# rf_lpf_60_40.net
KiCad netlist of a schematic drawn in Altium Designer
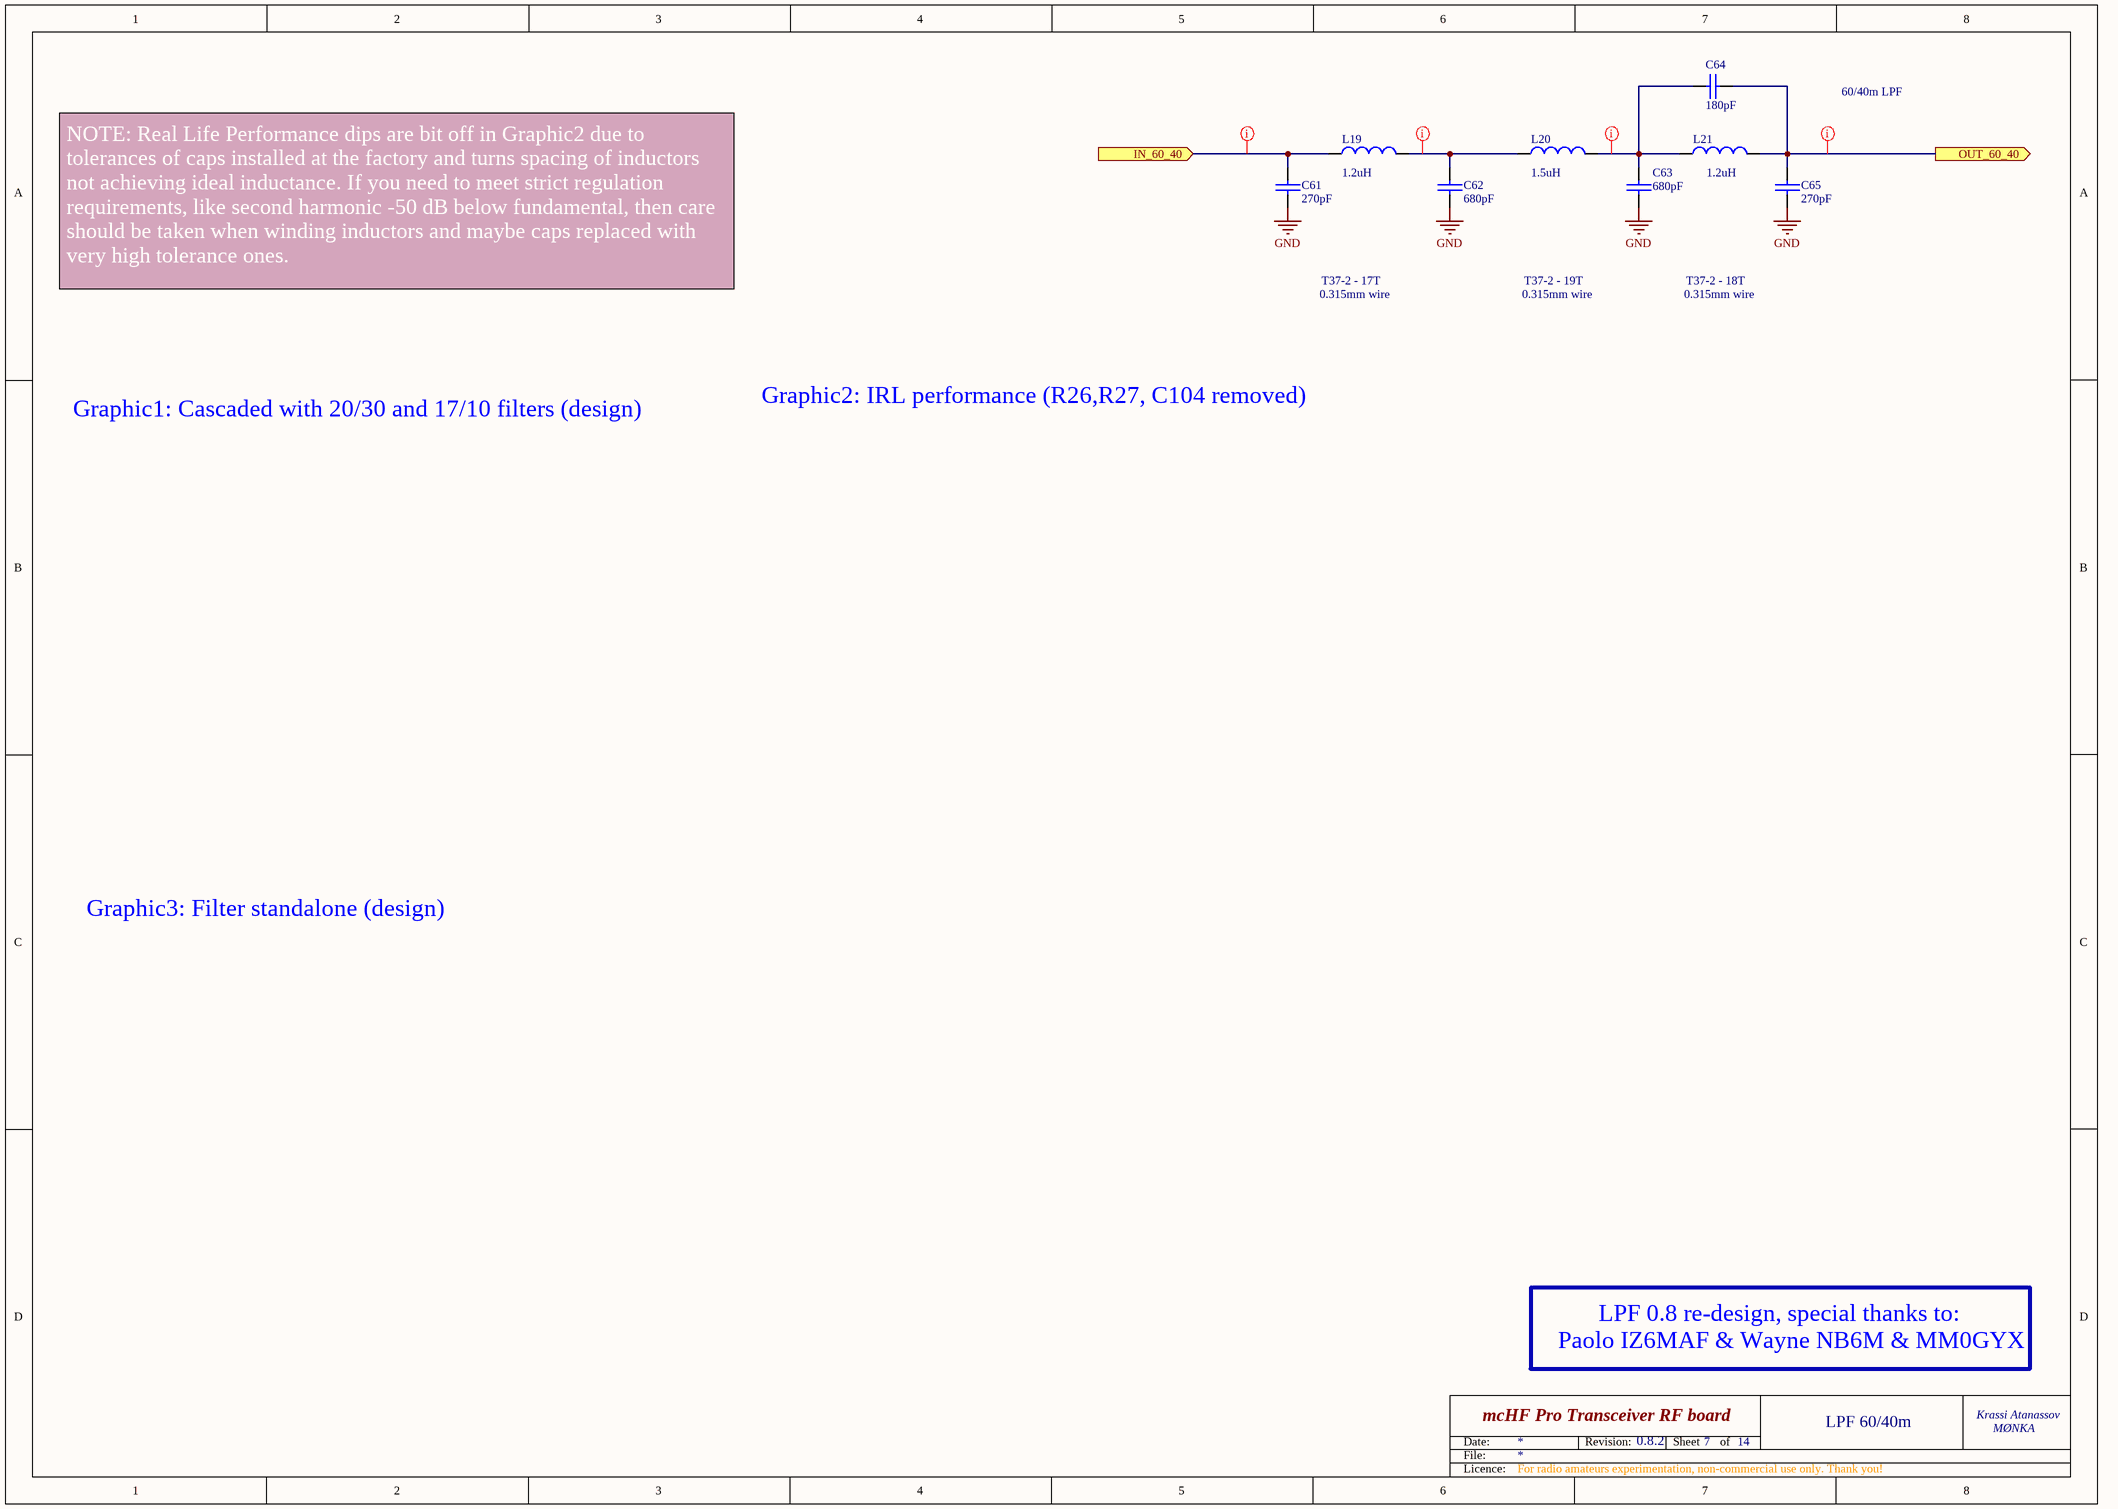
[diagram p0: rf_lpf_60_40.SchDoc]

(export (version "E")
  (design (tool "Eeschema 10.0.6"))
  (components
    (comp (ref "C61")
      (value "270pF")
      (footprint "0805")
      (description "Capacitor")
      (fields (field (name "VOLTAGE") "100V"))
      (libsource (lib "mcHF_rf") (part "CAP"))
    )
    (comp (ref "C62")
      (value "680pF")
      (footprint "0805")
      (description "Capacitor")
      (fields (field (name "VOLTAGE") "100V"))
      (libsource (lib "mcHF_rf") (part "CAP"))
    )
    (comp (ref "C63")
      (value "680pF")
      (footprint "0805")
      (description "Capacitor")
      (fields (field (name "VOLTAGE") "100V"))
      (libsource (lib "mcHF_rf") (part "CAP"))
    )
    (comp (ref "C64")
      (value "180pF")
      (footprint "0805")
      (description "Capacitor")
      (fields (field (name "VOLTAGE") "100V"))
      (libsource (lib "mcHF_rf") (part "CAP"))
    )
    (comp (ref "C65")
      (value "270pF")
      (footprint "0805")
      (description "Capacitor")
      (fields (field (name "VOLTAGE") "100V"))
      (libsource (lib "mcHF_rf") (part "CAP"))
    )
    (comp (ref "L19")
      (value "T37-2")
      (footprint "LPF_IND")
      (description "T37-2 handwound inductor")
      (fields (field (name "INDUCTANCE") "1.2uH"))
      (libsource (lib "mcHF_rf") (part "LPF_IND"))
    )
    (comp (ref "L20")
      (value "T37-2")
      (footprint "LPF_IND")
      (description "T37-2 handwound inductor")
      (fields (field (name "INDUCTANCE") "1.5uH"))
      (libsource (lib "mcHF_rf") (part "LPF_IND"))
    )
    (comp (ref "L21")
      (value "T37-2")
      (footprint "LPF_IND")
      (description "T37-2 handwound inductor")
      (fields (field (name "INDUCTANCE") "1.2uH"))
      (libsource (lib "mcHF_rf") (part "LPF_IND"))
    )
  )
  (nets
    (net (code "1") (name "/IN_60_40") (class "Default")
      (node (ref "C61") (pin "2") (pinfunction "2_2") (pintype "passive"))
      (node (ref "L19") (pin "1") (pinfunction "1_1") (pintype "passive"))
    )
    (net (code "2") (name "/OUT_60_40") (class "Default")
      (node (ref "C64") (pin "1") (pinfunction "1_1") (pintype "passive"))
      (node (ref "C65") (pin "2") (pinfunction "2_2") (pintype "passive"))
      (node (ref "L21") (pin "2") (pinfunction "2_2") (pintype "passive"))
    )
    (net (code "3") (name "GND") (class "Default")
      (node (ref "C61") (pin "1") (pinfunction "1_1") (pintype "passive"))
      (node (ref "C62") (pin "1") (pinfunction "1_1") (pintype "passive"))
      (node (ref "C63") (pin "1") (pinfunction "1_1") (pintype "passive"))
      (node (ref "C65") (pin "1") (pinfunction "1_1") (pintype "passive"))
    )
    (net (code "4") (name "Net-(C62-Pad2)") (class "Default")
      (node (ref "C62") (pin "2") (pinfunction "2_2") (pintype "passive"))
      (node (ref "L19") (pin "2") (pinfunction "2_2") (pintype "passive"))
      (node (ref "L20") (pin "1") (pinfunction "1_1") (pintype "passive"))
    )
    (net (code "5") (name "Net-(C63-Pad2)") (class "Default")
      (node (ref "C63") (pin "2") (pinfunction "2_2") (pintype "passive"))
      (node (ref "C64") (pin "2") (pinfunction "2_2") (pintype "passive"))
      (node (ref "L20") (pin "2") (pinfunction "2_2") (pintype "passive"))
      (node (ref "L21") (pin "1") (pinfunction "1_1") (pintype "passive"))
    )
  )
)
